# Position_potmeter.net
KiCad netlist of a schematic drawn in EAGLE
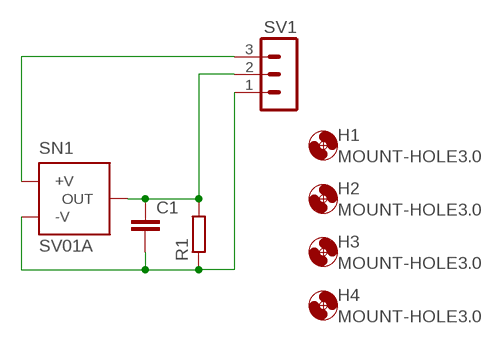
[diagram p0: schematic, sheet 1]

(export (version "E")
  (design (tool "Eeschema 10.0.6"))
  (components
    (comp (ref "C1")
      (value "C-EUC0805K")
      (footprint "eagle-import:C0805K")
      (libsource (lib "eagle-import") (part "C-EUC0805K"))
    )
    (comp (ref "H1")
      (value "MOUNT-HOLE3.0")
      (footprint "eagle-import:3,0")
      (libsource (lib "eagle-import") (part "MOUNT-HOLE3.0"))
    )
    (comp (ref "H2")
      (value "MOUNT-HOLE3.0")
      (footprint "eagle-import:3,0")
      (libsource (lib "eagle-import") (part "MOUNT-HOLE3.0"))
    )
    (comp (ref "H3")
      (value "MOUNT-HOLE3.0")
      (footprint "eagle-import:3,0")
      (libsource (lib "eagle-import") (part "MOUNT-HOLE3.0"))
    )
    (comp (ref "H4")
      (value "MOUNT-HOLE3.0")
      (footprint "eagle-import:3,0")
      (libsource (lib "eagle-import") (part "MOUNT-HOLE3.0"))
    )
    (comp (ref "R1")
      (value "R-EU_M0805")
      (footprint "eagle-import:M0805")
      (libsource (lib "eagle-import") (part "R-EU_M0805"))
    )
    (comp (ref "SN1")
      (value "SV01A")
      (footprint "eagle-import:SV01A")
      (libsource (lib "eagle-import") (part "SV01A"))
    )
    (comp (ref "SV1")
      (value "MA03-1")
      (footprint "eagle-import:MA03-1")
      (libsource (lib "eagle-import") (part "MA03-1"))
    )
  )
  (nets
    (net (code "1") (name "Net-(SN1-+V)") (class "Default")
      (node (ref "SN1") (pin "3") (pinfunction "+V_3") (pintype "passive"))
      (node (ref "SV1") (pin "3") (pinfunction "3_3") (pintype "passive"))
    )
    (net (code "2") (name "Net-(SN1--V)") (class "Default")
      (node (ref "C1") (pin "2") (pinfunction "2_2") (pintype "passive"))
      (node (ref "R1") (pin "1") (pinfunction "1_1") (pintype "passive"))
      (node (ref "SN1") (pin "1") (pinfunction "-V_1") (pintype "passive"))
      (node (ref "SV1") (pin "1") (pinfunction "1_1") (pintype "passive"))
    )
    (net (code "3") (name "Net-(SN1-OUT)") (class "Default")
      (node (ref "C1") (pin "1") (pinfunction "1_1") (pintype "passive"))
      (node (ref "R1") (pin "2") (pinfunction "2_2") (pintype "passive"))
      (node (ref "SN1") (pin "2") (pinfunction "OUT_2") (pintype "passive"))
      (node (ref "SV1") (pin "2") (pinfunction "2_2") (pintype "passive"))
    )
  )
)
